# regulator.net
KiCad netlist of a schematic drawn in EAGLE
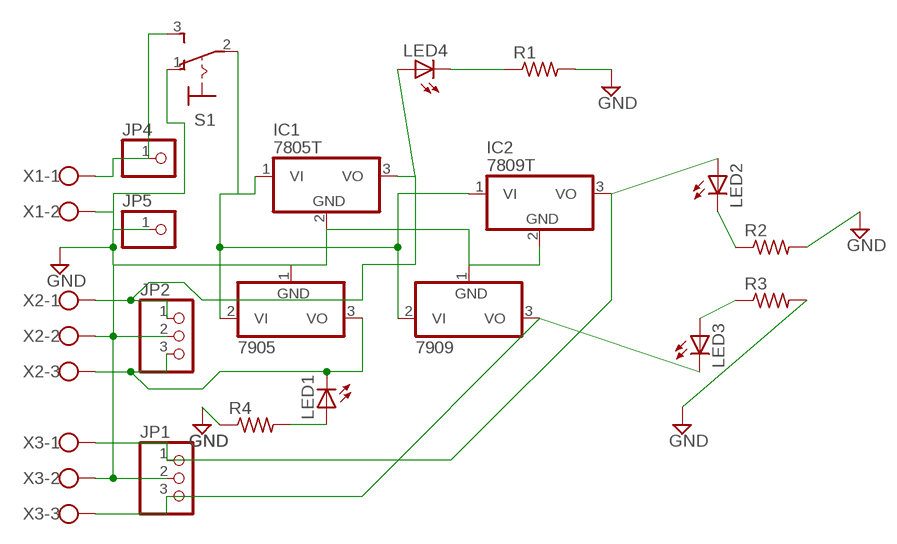
[diagram p0: schematic, sheet 1]

(export (version "E")
  (design (tool "Eeschema 10.0.6"))
  (components
    (comp (ref "7905")
      (value "7905T")
      (footprint "eagle-import:TO220H")
      (libsource (lib "eagle-import") (part "79T05"))
    )
    (comp (ref "7909")
      (value "7905T")
      (footprint "eagle-import:TO220H")
      (libsource (lib "eagle-import") (part "79T05"))
    )
    (comp (ref "IC1")
      (value "7805T")
      (footprint "eagle-import:TO220H")
      (libsource (lib "eagle-import") (part "78T05"))
    )
    (comp (ref "IC2")
      (value "7809T")
      (footprint "eagle-import:TO220H")
      (libsource (lib "eagle-import") (part "78T05"))
    )
    (comp (ref "JP1")
      (value "PINHD-1X3CB")
      (footprint "eagle-import:1X03-CLEANBIG")
      (libsource (lib "eagle-import") (part "PINHD-1X3CB"))
    )
    (comp (ref "JP2")
      (value "PINHD-1X3CB")
      (footprint "eagle-import:1X03-CLEANBIG")
      (libsource (lib "eagle-import") (part "PINHD-1X3CB"))
    )
    (comp (ref "JP4")
      (value "PINHD-1X1CB")
      (footprint "eagle-import:1X01-CLEANBIG")
      (libsource (lib "eagle-import") (part "PINHD-1X1CB"))
    )
    (comp (ref "JP5")
      (value "PINHD-1X1CB")
      (footprint "eagle-import:1X01-CLEANBIG")
      (libsource (lib "eagle-import") (part "PINHD-1X1CB"))
    )
    (comp (ref "LED1")
      (value "LED3MM")
      (footprint "eagle-import:LED3MM")
      (libsource (lib "eagle-import") (part "LED3MM"))
    )
    (comp (ref "LED2")
      (value "LED3MM")
      (footprint "eagle-import:LED3MM")
      (libsource (lib "eagle-import") (part "LED3MM"))
    )
    (comp (ref "LED3")
      (value "LED3MM")
      (footprint "eagle-import:LED3MM")
      (libsource (lib "eagle-import") (part "LED3MM"))
    )
    (comp (ref "LED4")
      (value "LED3MM")
      (footprint "eagle-import:LED3MM")
      (libsource (lib "eagle-import") (part "LED3MM"))
    )
    (comp (ref "R1")
      (value "R-US_0309/10")
      (footprint "eagle-import:0309_10")
      (libsource (lib "eagle-import") (part "R-US_0309/10"))
    )
    (comp (ref "R2")
      (value "R-US_0309/10")
      (footprint "eagle-import:0309_10")
      (libsource (lib "eagle-import") (part "R-US_0309/10"))
    )
    (comp (ref "R3")
      (value "R-US_0309/10")
      (footprint "eagle-import:0309_10")
      (libsource (lib "eagle-import") (part "R-US_0309/10"))
    )
    (comp (ref "R4")
      (value "R-US_0309/10")
      (footprint "eagle-import:0309_10")
      (libsource (lib "eagle-import") (part "R-US_0309/10"))
    )
    (comp (ref "S1")
      (value "320-916")
      (footprint "eagle-import:320-916")
      (libsource (lib "eagle-import") (part "320-916"))
    )
    (comp (ref "X1")
      (value "W237-102")
      (footprint "eagle-import:W237-102")
      (fields (field (name "MPN") "237-102"))
      (libsource (lib "eagle-import") (part "W237-102"))
    )
    (comp (ref "X2")
      (value "W237-103")
      (footprint "eagle-import:W237-103")
      (fields (field (name "MPN") "237-103"))
      (libsource (lib "eagle-import") (part "W237-103"))
    )
    (comp (ref "X3")
      (value "W237-103")
      (footprint "eagle-import:W237-103")
      (fields (field (name "MPN") "237-103"))
      (libsource (lib "eagle-import") (part "W237-103"))
    )
  )
  (nets
    (net (code "1") (name "GND") (class "Default")
      (node (ref "7905") (pin "1") (pinfunction "GND_1") (pintype "passive"))
      (node (ref "7909") (pin "1") (pinfunction "GND_1") (pintype "passive"))
      (node (ref "IC1") (pin "2") (pinfunction "GND_2") (pintype "passive"))
      (node (ref "IC2") (pin "2") (pinfunction "GND_2") (pintype "passive"))
      (node (ref "JP1") (pin "2") (pinfunction "2_2") (pintype "passive"))
      (node (ref "JP2") (pin "2") (pinfunction "2_2") (pintype "passive"))
      (node (ref "JP5") (pin "1") (pinfunction "1_1") (pintype "passive"))
      (node (ref "R1") (pin "2") (pinfunction "2_2") (pintype "passive"))
      (node (ref "R2") (pin "2") (pinfunction "2_2") (pintype "passive"))
      (node (ref "R3") (pin "2") (pinfunction "2_2") (pintype "passive"))
      (node (ref "R4") (pin "1") (pinfunction "1_1") (pintype "passive"))
      (node (ref "S1") (pin "1") (pinfunction "O_1") (pintype "passive"))
      (node (ref "X1") (pin "2") (pinfunction "KL_2") (pintype "passive"))
      (node (ref "X2") (pin "2") (pinfunction "KL_2") (pintype "passive"))
      (node (ref "X3") (pin "2") (pinfunction "KL_2") (pintype "passive"))
    )
    (net (code "2") (name "Net-(7905-VI)") (class "Default")
      (node (ref "7905") (pin "2") (pinfunction "VI_2") (pintype "input"))
      (node (ref "7909") (pin "2") (pinfunction "VI_2") (pintype "input"))
      (node (ref "IC1") (pin "1") (pinfunction "VI_1") (pintype "input"))
      (node (ref "IC2") (pin "1") (pinfunction "VI_1") (pintype "input"))
      (node (ref "S1") (pin "2") (pinfunction "P_2") (pintype "passive"))
    )
    (net (code "3") (name "Net-(7905-VO)") (class "Default")
      (node (ref "7905") (pin "3") (pinfunction "VO_3") (pintype "passive"))
      (node (ref "JP2") (pin "3") (pinfunction "3_3") (pintype "passive"))
      (node (ref "LED1") (pin "K") (pinfunction "C_K") (pintype "passive"))
      (node (ref "X2") (pin "3") (pinfunction "KL_3") (pintype "passive"))
    )
    (net (code "4") (name "Net-(7909-VO)") (class "Default")
      (node (ref "7909") (pin "3") (pinfunction "VO_3") (pintype "passive"))
      (node (ref "JP1") (pin "3") (pinfunction "3_3") (pintype "passive"))
      (node (ref "LED3") (pin "K") (pinfunction "C_K") (pintype "passive"))
      (node (ref "X3") (pin "3") (pinfunction "KL_3") (pintype "passive"))
    )
    (net (code "5") (name "Net-(IC1-VO)") (class "Default")
      (node (ref "IC1") (pin "3") (pinfunction "VO_3") (pintype "passive"))
      (node (ref "JP2") (pin "1") (pinfunction "1_1") (pintype "passive"))
      (node (ref "LED4") (pin "A") (pinfunction "A_A") (pintype "passive"))
      (node (ref "X2") (pin "1") (pinfunction "KL_1") (pintype "passive"))
    )
    (net (code "6") (name "Net-(IC2-VO)") (class "Default")
      (node (ref "IC2") (pin "3") (pinfunction "VO_3") (pintype "passive"))
      (node (ref "JP1") (pin "1") (pinfunction "1_1") (pintype "passive"))
      (node (ref "LED2") (pin "A") (pinfunction "A_A") (pintype "passive"))
      (node (ref "X3") (pin "1") (pinfunction "KL_1") (pintype "passive"))
    )
    (net (code "7") (name "Net-(LED1-PadA)") (class "Default")
      (node (ref "LED1") (pin "A") (pinfunction "A_A") (pintype "passive"))
      (node (ref "R4") (pin "2") (pinfunction "2_2") (pintype "passive"))
    )
    (net (code "8") (name "Net-(LED2-C)") (class "Default")
      (node (ref "LED2") (pin "K") (pinfunction "C_K") (pintype "passive"))
      (node (ref "R2") (pin "1") (pinfunction "1_1") (pintype "passive"))
    )
    (net (code "9") (name "Net-(LED3-PadA)") (class "Default")
      (node (ref "LED3") (pin "A") (pinfunction "A_A") (pintype "passive"))
      (node (ref "R3") (pin "1") (pinfunction "1_1") (pintype "passive"))
    )
    (net (code "10") (name "Net-(LED4-C)") (class "Default")
      (node (ref "LED4") (pin "K") (pinfunction "C_K") (pintype "passive"))
      (node (ref "R1") (pin "1") (pinfunction "1_1") (pintype "passive"))
    )
    (net (code "11") (name "Net-(S1-S)") (class "Default")
      (node (ref "JP4") (pin "1") (pinfunction "1_1") (pintype "passive"))
      (node (ref "S1") (pin "3") (pinfunction "S_3") (pintype "passive"))
      (node (ref "X1") (pin "1") (pinfunction "KL_1") (pintype "passive"))
    )
  )
)
